# W5500_Tessel_mikroBUS_Click_005.net
KiCad netlist of a schematic drawn in EAGLE
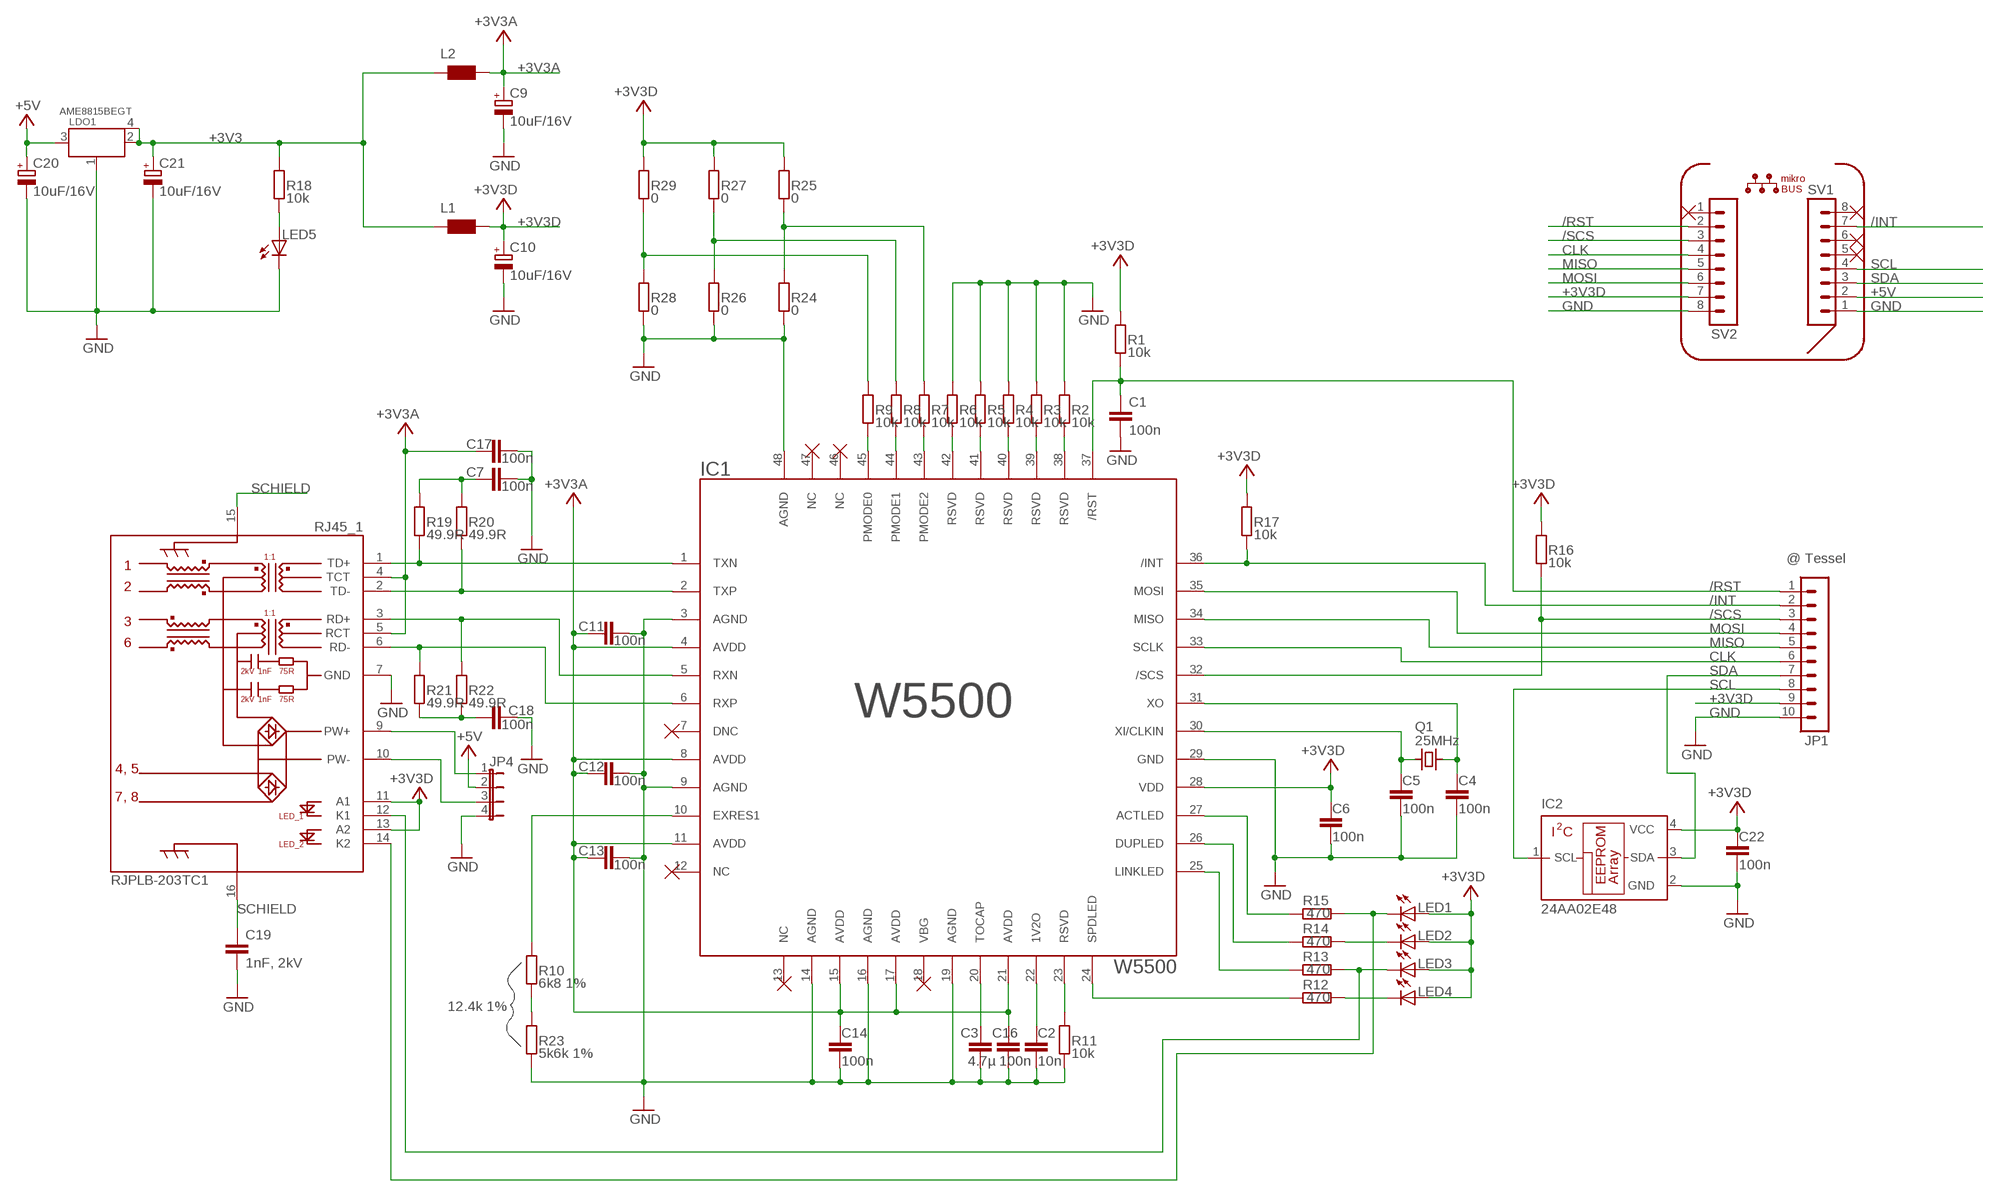
[diagram p0: schematic, sheet 1]

(export (version "E")
  (design (tool "Eeschema 10.0.6"))
  (components
    (comp (ref "C1")
      (value "100n")
      (footprint "eagle-import:C0603K")
      (libsource (lib "eagle-import") (part "C-EUC0603K"))
    )
    (comp (ref "C2")
      (value "10n")
      (footprint "eagle-import:C0402K")
      (libsource (lib "eagle-import") (part "C-EUC0402K"))
    )
    (comp (ref "C3")
      (value "4.7µ")
      (footprint "eagle-import:C0603K")
      (libsource (lib "eagle-import") (part "C-EUC0603K"))
    )
    (comp (ref "C4")
      (value "100n")
      (footprint "eagle-import:C0402K")
      (libsource (lib "eagle-import") (part "C-EUC0402K"))
    )
    (comp (ref "C5")
      (value "100n")
      (footprint "eagle-import:C0402K")
      (libsource (lib "eagle-import") (part "C-EUC0402K"))
    )
    (comp (ref "C6")
      (value "100n")
      (footprint "eagle-import:C0402K")
      (libsource (lib "eagle-import") (part "C-EUC0402K"))
    )
    (comp (ref "C7")
      (value "100n")
      (footprint "eagle-import:C0402K")
      (libsource (lib "eagle-import") (part "C-EUC0402K"))
    )
    (comp (ref "C9")
      (value "10uF/16V")
      (footprint "eagle-import:A_3216-18R")
      (libsource (lib "eagle-import") (part "CPOL-EUA/3216-18R"))
    )
    (comp (ref "C10")
      (value "10uF/16V")
      (footprint "eagle-import:A_3216-18R")
      (libsource (lib "eagle-import") (part "CPOL-EUA/3216-18R"))
    )
    (comp (ref "C11")
      (value "100n")
      (footprint "eagle-import:C0402K")
      (libsource (lib "eagle-import") (part "C-EUC0402K"))
    )
    (comp (ref "C12")
      (value "100n")
      (footprint "eagle-import:C0402K")
      (libsource (lib "eagle-import") (part "C-EUC0402K"))
    )
    (comp (ref "C13")
      (value "100n")
      (footprint "eagle-import:C0402K")
      (libsource (lib "eagle-import") (part "C-EUC0402K"))
    )
    (comp (ref "C14")
      (value "100n")
      (footprint "eagle-import:C0402K")
      (libsource (lib "eagle-import") (part "C-EUC0402K"))
    )
    (comp (ref "C16")
      (value "100n")
      (footprint "eagle-import:C0402K")
      (libsource (lib "eagle-import") (part "C-EUC0402K"))
    )
    (comp (ref "C17")
      (value "100n")
      (footprint "eagle-import:C0402K")
      (libsource (lib "eagle-import") (part "C-EUC0402K"))
    )
    (comp (ref "C18")
      (value "100n")
      (footprint "eagle-import:C0402K")
      (libsource (lib "eagle-import") (part "C-EUC0402K"))
    )
    (comp (ref "C19")
      (value "1nF, 2kV")
      (footprint "eagle-import:C3216")
      (libsource (lib "eagle-import") (part "C-EUC3216"))
    )
    (comp (ref "C20")
      (value "10uF/16V")
      (footprint "eagle-import:A_3216-18R")
      (libsource (lib "eagle-import") (part "CPOL-EUA/3216-18R"))
    )
    (comp (ref "C21")
      (value "10uF/16V")
      (footprint "eagle-import:A_3216-18R")
      (libsource (lib "eagle-import") (part "CPOL-EUA/3216-18R"))
    )
    (comp (ref "C22")
      (value "100n")
      (footprint "eagle-import:C0402K")
      (libsource (lib "eagle-import") (part "C-EUC0402K"))
    )
    (comp (ref "IC1")
      (value "W5500")
      (footprint "eagle-import:LQFP48")
      (libsource (lib "eagle-import") (part "W5500"))
    )
    (comp (ref "IC2")
      (value "24AA02E48")
      (footprint "eagle-import:SOT23-5L")
      (fields (field (name "MF") "MICROCHIP") (field (name "MPN") "24AA00T-I/OTG"))
      (libsource (lib "eagle-import") (part "2400OTAA"))
    )
    (comp (ref "JP1")
      (value "@ Tessel")
      (footprint "eagle-import:MA10-1")
      (libsource (lib "eagle-import") (part "MA10-1"))
    )
    (comp (ref "JP4")
      (value "JP4E")
      (footprint "eagle-import:JP4")
      (libsource (lib "eagle-import") (part "JP4E"))
    )
    (comp (ref "L1")
      (value "WE-CBF_0603")
      (footprint "eagle-import:0603")
      (libsource (lib "eagle-import") (part "WE-CBF_0603"))
    )
    (comp (ref "L2")
      (value "WE-CBF_0603")
      (footprint "eagle-import:0603")
      (libsource (lib "eagle-import") (part "WE-CBF_0603"))
    )
    (comp (ref "LDO1")
      (value "AME8815BEGT")
      (footprint "eagle-import:SOT223")
      (libsource (lib "eagle-import") (part "AME8815BEGT"))
    )
    (comp (ref "LED1")
      (value "LEDCHIPLED_0603")
      (footprint "eagle-import:CHIPLED_0603")
      (libsource (lib "eagle-import") (part "LEDCHIPLED_0603"))
    )
    (comp (ref "LED2")
      (value "LEDCHIPLED_0603")
      (footprint "eagle-import:CHIPLED_0603")
      (libsource (lib "eagle-import") (part "LEDCHIPLED_0603"))
    )
    (comp (ref "LED3")
      (value "LEDCHIPLED_0603")
      (footprint "eagle-import:CHIPLED_0603")
      (libsource (lib "eagle-import") (part "LEDCHIPLED_0603"))
    )
    (comp (ref "LED4")
      (value "LEDCHIPLED_0603")
      (footprint "eagle-import:CHIPLED_0603")
      (libsource (lib "eagle-import") (part "LEDCHIPLED_0603"))
    )
    (comp (ref "LED5")
      (value "LEDCHIPLED_0603")
      (footprint "eagle-import:CHIPLED_0603")
      (libsource (lib "eagle-import") (part "LEDCHIPLED_0603"))
    )
    (comp (ref "Q1")
      (value "25MHz")
      (footprint "eagle-import:SMD02502-4")
      (libsource (lib "eagle-import") (part "SMD02502-4"))
    )
    (comp (ref "R1")
      (value "10k")
      (footprint "eagle-import:R0402")
      (libsource (lib "eagle-import") (part "R-EU_R0402"))
    )
    (comp (ref "R2")
      (value "10k")
      (footprint "eagle-import:R0402")
      (libsource (lib "eagle-import") (part "R-EU_R0402"))
    )
    (comp (ref "R3")
      (value "10k")
      (footprint "eagle-import:R0402")
      (libsource (lib "eagle-import") (part "R-EU_R0402"))
    )
    (comp (ref "R4")
      (value "10k")
      (footprint "eagle-import:R0402")
      (libsource (lib "eagle-import") (part "R-EU_R0402"))
    )
    (comp (ref "R5")
      (value "10k")
      (footprint "eagle-import:R0402")
      (libsource (lib "eagle-import") (part "R-EU_R0402"))
    )
    (comp (ref "R6")
      (value "10k")
      (footprint "eagle-import:R0402")
      (libsource (lib "eagle-import") (part "R-EU_R0402"))
    )
    (comp (ref "R7")
      (value "10k")
      (footprint "eagle-import:R0402")
      (libsource (lib "eagle-import") (part "R-EU_R0402"))
    )
    (comp (ref "R8")
      (value "10k")
      (footprint "eagle-import:R0402")
      (libsource (lib "eagle-import") (part "R-EU_R0402"))
    )
    (comp (ref "R9")
      (value "10k")
      (footprint "eagle-import:R0402")
      (libsource (lib "eagle-import") (part "R-EU_R0402"))
    )
    (comp (ref "R10")
      (value "6k8 1%")
      (footprint "eagle-import:R0402")
      (libsource (lib "eagle-import") (part "R-EU_R0402"))
    )
    (comp (ref "R11")
      (value "10k")
      (footprint "eagle-import:R0402")
      (libsource (lib "eagle-import") (part "R-EU_R0402"))
    )
    (comp (ref "R12")
      (value "470")
      (footprint "eagle-import:R0402")
      (libsource (lib "eagle-import") (part "R-EU_R0402"))
    )
    (comp (ref "R13")
      (value "470")
      (footprint "eagle-import:R0402")
      (libsource (lib "eagle-import") (part "R-EU_R0402"))
    )
    (comp (ref "R14")
      (value "470")
      (footprint "eagle-import:R0402")
      (libsource (lib "eagle-import") (part "R-EU_R0402"))
    )
    (comp (ref "R15")
      (value "470")
      (footprint "eagle-import:R0402")
      (libsource (lib "eagle-import") (part "R-EU_R0402"))
    )
    (comp (ref "R16")
      (value "10k")
      (footprint "eagle-import:R0402")
      (libsource (lib "eagle-import") (part "R-EU_R0402"))
    )
    (comp (ref "R17")
      (value "10k")
      (footprint "eagle-import:R0402")
      (libsource (lib "eagle-import") (part "R-EU_R0402"))
    )
    (comp (ref "R18")
      (value "10k")
      (footprint "eagle-import:R0402")
      (libsource (lib "eagle-import") (part "R-EU_R0402"))
    )
    (comp (ref "R19")
      (value "49.9R")
      (footprint "eagle-import:R0402")
      (libsource (lib "eagle-import") (part "R-EU_R0402"))
    )
    (comp (ref "R20")
      (value "49.9R")
      (footprint "eagle-import:R0402")
      (libsource (lib "eagle-import") (part "R-EU_R0402"))
    )
    (comp (ref "R21")
      (value "49.9R")
      (footprint "eagle-import:R0402")
      (libsource (lib "eagle-import") (part "R-EU_R0402"))
    )
    (comp (ref "R22")
      (value "49.9R")
      (footprint "eagle-import:R0402")
      (libsource (lib "eagle-import") (part "R-EU_R0402"))
    )
    (comp (ref "R23")
      (value "5k6k 1%")
      (footprint "eagle-import:R0402")
      (libsource (lib "eagle-import") (part "R-EU_R0402"))
    )
    (comp (ref "R24")
      (value "0")
      (footprint "eagle-import:R0402")
      (libsource (lib "eagle-import") (part "R-EU_R0402"))
    )
    (comp (ref "R25")
      (value "0")
      (footprint "eagle-import:R0402")
      (libsource (lib "eagle-import") (part "R-EU_R0402"))
    )
    (comp (ref "R26")
      (value "0")
      (footprint "eagle-import:R0402")
      (libsource (lib "eagle-import") (part "R-EU_R0402"))
    )
    (comp (ref "R27")
      (value "0")
      (footprint "eagle-import:R0402")
      (libsource (lib "eagle-import") (part "R-EU_R0402"))
    )
    (comp (ref "R28")
      (value "0")
      (footprint "eagle-import:R0402")
      (libsource (lib "eagle-import") (part "R-EU_R0402"))
    )
    (comp (ref "R29")
      (value "0")
      (footprint "eagle-import:R0402")
      (libsource (lib "eagle-import") (part "R-EU_R0402"))
    )
    (comp (ref "RJ45_1")
      (value "RJPLB-203TC1")
      (footprint "eagle-import:RJPLB-203")
      (libsource (lib "eagle-import") (part "RJPLB-203TC1"))
    )
    (comp (ref "SV1")
      (value "MA08-1")
      (footprint "eagle-import:MA08-1")
      (libsource (lib "eagle-import") (part "MA08-1"))
    )
    (comp (ref "SV2")
      (value "MA08-1")
      (footprint "eagle-import:MA08-1")
      (libsource (lib "eagle-import") (part "MA08-1"))
    )
  )
  (nets
    (net (code "1") (name "+3V3A") (class "Default")
      (node (ref "C11") (pin "1") (pinfunction "1_1") (pintype "passive"))
      (node (ref "C12") (pin "1") (pinfunction "1_1") (pintype "passive"))
      (node (ref "C13") (pin "1") (pinfunction "1_1") (pintype "passive"))
      (node (ref "C14") (pin "1") (pinfunction "1_1") (pintype "passive"))
      (node (ref "C16") (pin "1") (pinfunction "1_1") (pintype "passive"))
      (node (ref "C17") (pin "1") (pinfunction "1_1") (pintype "passive"))
      (node (ref "C9") (pin "+") (pinfunction "+_+") (pintype "passive"))
      (node (ref "IC1") (pin "11") (pinfunction "AVDD_11") (pintype "bidirectional"))
      (node (ref "IC1") (pin "15") (pinfunction "AVDD_15") (pintype "bidirectional"))
      (node (ref "IC1") (pin "17") (pinfunction "AVDD_17") (pintype "bidirectional"))
      (node (ref "IC1") (pin "21") (pinfunction "AVDD_21") (pintype "bidirectional"))
      (node (ref "IC1") (pin "4") (pinfunction "AVDD_4") (pintype "bidirectional"))
      (node (ref "IC1") (pin "8") (pinfunction "AVDD_8") (pintype "bidirectional"))
      (node (ref "L2") (pin "1") (pinfunction "1_1") (pintype "passive"))
      (node (ref "RJ45_1") (pin "4") (pinfunction "TCT_4") (pintype "bidirectional"))
      (node (ref "RJ45_1") (pin "5") (pinfunction "RCT_5") (pintype "bidirectional"))
    )
    (net (code "2") (name "+3V3D") (class "Default")
      (node (ref "C10") (pin "+") (pinfunction "+_+") (pintype "passive"))
      (node (ref "C22") (pin "1") (pinfunction "1_1") (pintype "passive"))
      (node (ref "C6") (pin "1") (pinfunction "1_1") (pintype "passive"))
      (node (ref "IC1") (pin "28") (pinfunction "VDD_28") (pintype "bidirectional"))
      (node (ref "IC2") (pin "4") (pinfunction "VCC_4") (pintype "power_in"))
      (node (ref "JP1") (pin "9") (pinfunction "9_9") (pintype "passive"))
      (node (ref "L1") (pin "1") (pinfunction "1_1") (pintype "passive"))
      (node (ref "LED1") (pin "A") (pinfunction "A_A") (pintype "passive"))
      (node (ref "LED2") (pin "A") (pinfunction "A_A") (pintype "passive"))
      (node (ref "LED3") (pin "A") (pinfunction "A_A") (pintype "passive"))
      (node (ref "LED4") (pin "A") (pinfunction "A_A") (pintype "passive"))
      (node (ref "R1") (pin "2") (pinfunction "2_2") (pintype "passive"))
      (node (ref "R16") (pin "2") (pinfunction "2_2") (pintype "passive"))
      (node (ref "R17") (pin "2") (pinfunction "2_2") (pintype "passive"))
      (node (ref "R25") (pin "2") (pinfunction "2_2") (pintype "passive"))
      (node (ref "R27") (pin "2") (pinfunction "2_2") (pintype "passive"))
      (node (ref "R29") (pin "2") (pinfunction "2_2") (pintype "passive"))
      (node (ref "RJ45_1") (pin "11") (pinfunction "A1_11") (pintype "bidirectional"))
      (node (ref "RJ45_1") (pin "13") (pinfunction "A2_13") (pintype "bidirectional"))
      (node (ref "SV2") (pin "7") (pinfunction "7_7") (pintype "passive"))
    )
    (net (code "3") (name "+5V") (class "Default")
      (node (ref "C20") (pin "+") (pinfunction "+_+") (pintype "passive"))
      (node (ref "JP4") (pin "2") (pinfunction "2_2") (pintype "passive"))
      (node (ref "LDO1") (pin "3") (pinfunction "P$3_3") (pintype "bidirectional"))
      (node (ref "SV1") (pin "2") (pinfunction "2_2") (pintype "passive"))
    )
    (net (code "4") (name "/+3V3") (class "Default")
      (node (ref "C21") (pin "+") (pinfunction "+_+") (pintype "passive"))
      (node (ref "L1") (pin "2") (pinfunction "2_2") (pintype "passive"))
      (node (ref "L2") (pin "2") (pinfunction "2_2") (pintype "passive"))
      (node (ref "LDO1") (pin "2") (pinfunction "P$2_2") (pintype "bidirectional"))
      (node (ref "LDO1") (pin "4") (pinfunction "P$4_4") (pintype "bidirectional"))
      (node (ref "R18") (pin "2") (pinfunction "2_2") (pintype "passive"))
    )
    (net (code "5") (name "/CLK") (class "Default")
      (node (ref "IC1") (pin "33") (pinfunction "SCLK_33") (pintype "bidirectional"))
      (node (ref "JP1") (pin "6") (pinfunction "6_6") (pintype "passive"))
      (node (ref "SV2") (pin "4") (pinfunction "4_4") (pintype "passive"))
    )
    (net (code "6") (name "/MISO") (class "Default")
      (node (ref "IC1") (pin "34") (pinfunction "MISO_34") (pintype "bidirectional"))
      (node (ref "JP1") (pin "5") (pinfunction "5_5") (pintype "passive"))
      (node (ref "SV2") (pin "5") (pinfunction "5_5") (pintype "passive"))
    )
    (net (code "7") (name "/MOSI") (class "Default")
      (node (ref "IC1") (pin "35") (pinfunction "MOSI_35") (pintype "bidirectional"))
      (node (ref "JP1") (pin "4") (pinfunction "4_4") (pintype "passive"))
      (node (ref "SV2") (pin "6") (pinfunction "6_6") (pintype "passive"))
    )
    (net (code "8") (name "/SCHIELD") (class "Default")
      (node (ref "C19") (pin "1") (pinfunction "1_1") (pintype "passive"))
      (node (ref "RJ45_1") (pin "15") (pinfunction "SCHIELD_1_15") (pintype "bidirectional"))
      (node (ref "RJ45_1") (pin "16") (pinfunction "SCHIELD_2_16") (pintype "bidirectional"))
    )
    (net (code "9") (name "/SCL") (class "Default")
      (node (ref "IC2") (pin "1") (pinfunction "SCL_1") (pintype "input"))
      (node (ref "JP1") (pin "8") (pinfunction "8_8") (pintype "passive"))
      (node (ref "SV1") (pin "4") (pinfunction "4_4") (pintype "passive"))
    )
    (net (code "10") (name "/SDA") (class "Default")
      (node (ref "IC2") (pin "3") (pinfunction "SDA_3") (pintype "bidirectional"))
      (node (ref "JP1") (pin "7") (pinfunction "7_7") (pintype "passive"))
      (node (ref "SV1") (pin "3") (pinfunction "3_3") (pintype "passive"))
    )
    (net (code "11") (name "/{slash}INT") (class "Default")
      (node (ref "IC1") (pin "36") (pinfunction "/INT_36") (pintype "bidirectional"))
      (node (ref "JP1") (pin "2") (pinfunction "2_2") (pintype "passive"))
      (node (ref "R17") (pin "1") (pinfunction "1_1") (pintype "passive"))
      (node (ref "SV1") (pin "7") (pinfunction "7_7") (pintype "passive"))
    )
    (net (code "12") (name "/{slash}RST") (class "Default")
      (node (ref "C1") (pin "1") (pinfunction "1_1") (pintype "passive"))
      (node (ref "IC1") (pin "37") (pinfunction "/RST_37") (pintype "bidirectional"))
      (node (ref "JP1") (pin "1") (pinfunction "1_1") (pintype "passive"))
      (node (ref "R1") (pin "1") (pinfunction "1_1") (pintype "passive"))
      (node (ref "SV2") (pin "2") (pinfunction "2_2") (pintype "passive"))
    )
    (net (code "13") (name "/{slash}SCS") (class "Default")
      (node (ref "IC1") (pin "32") (pinfunction "/SCS_32") (pintype "bidirectional"))
      (node (ref "JP1") (pin "3") (pinfunction "3_3") (pintype "passive"))
      (node (ref "R16") (pin "1") (pinfunction "1_1") (pintype "passive"))
      (node (ref "SV2") (pin "3") (pinfunction "3_3") (pintype "passive"))
    )
    (net (code "14") (name "GND") (class "Default")
      (node (ref "C1") (pin "2") (pinfunction "2_2") (pintype "passive"))
      (node (ref "C10") (pin "-") (pinfunction "-_-") (pintype "passive"))
      (node (ref "C11") (pin "2") (pinfunction "2_2") (pintype "passive"))
      (node (ref "C12") (pin "2") (pinfunction "2_2") (pintype "passive"))
      (node (ref "C13") (pin "2") (pinfunction "2_2") (pintype "passive"))
      (node (ref "C14") (pin "2") (pinfunction "2_2") (pintype "passive"))
      (node (ref "C16") (pin "2") (pinfunction "2_2") (pintype "passive"))
      (node (ref "C17") (pin "2") (pinfunction "2_2") (pintype "passive"))
      (node (ref "C18") (pin "2") (pinfunction "2_2") (pintype "passive"))
      (node (ref "C19") (pin "2") (pinfunction "2_2") (pintype "passive"))
      (node (ref "C2") (pin "2") (pinfunction "2_2") (pintype "passive"))
      (node (ref "C20") (pin "-") (pinfunction "-_-") (pintype "passive"))
      (node (ref "C21") (pin "-") (pinfunction "-_-") (pintype "passive"))
      (node (ref "C22") (pin "2") (pinfunction "2_2") (pintype "passive"))
      (node (ref "C3") (pin "2") (pinfunction "2_2") (pintype "passive"))
      (node (ref "C4") (pin "2") (pinfunction "2_2") (pintype "passive"))
      (node (ref "C5") (pin "2") (pinfunction "2_2") (pintype "passive"))
      (node (ref "C6") (pin "2") (pinfunction "2_2") (pintype "passive"))
      (node (ref "C7") (pin "2") (pinfunction "2_2") (pintype "passive"))
      (node (ref "C9") (pin "-") (pinfunction "-_-") (pintype "passive"))
      (node (ref "IC1") (pin "14") (pinfunction "AGND_14") (pintype "bidirectional"))
      (node (ref "IC1") (pin "16") (pinfunction "AGND_16") (pintype "bidirectional"))
      (node (ref "IC1") (pin "19") (pinfunction "AGND_19") (pintype "bidirectional"))
      (node (ref "IC1") (pin "29") (pinfunction "GND_29") (pintype "bidirectional"))
      (node (ref "IC1") (pin "3") (pinfunction "AGND_3") (pintype "bidirectional"))
      (node (ref "IC1") (pin "48") (pinfunction "AGND_48") (pintype "bidirectional"))
      (node (ref "IC1") (pin "9") (pinfunction "AGND_9") (pintype "bidirectional"))
      (node (ref "IC2") (pin "2") (pinfunction "GND_2") (pintype "power_in"))
      (node (ref "JP1") (pin "10") (pinfunction "10_10") (pintype "passive"))
      (node (ref "JP4") (pin "4") (pinfunction "4_4") (pintype "passive"))
      (node (ref "LDO1") (pin "1") (pinfunction "P$1_1") (pintype "bidirectional"))
      (node (ref "LED5") (pin "C") (pinfunction "C_C") (pintype "passive"))
      (node (ref "R11") (pin "1") (pinfunction "1_1") (pintype "passive"))
      (node (ref "R2") (pin "2") (pinfunction "2_2") (pintype "passive"))
      (node (ref "R23") (pin "1") (pinfunction "1_1") (pintype "passive"))
      (node (ref "R24") (pin "1") (pinfunction "1_1") (pintype "passive"))
      (node (ref "R26") (pin "1") (pinfunction "1_1") (pintype "passive"))
      (node (ref "R28") (pin "1") (pinfunction "1_1") (pintype "passive"))
      (node (ref "R3") (pin "2") (pinfunction "2_2") (pintype "passive"))
      (node (ref "R4") (pin "2") (pinfunction "2_2") (pintype "passive"))
      (node (ref "R5") (pin "2") (pinfunction "2_2") (pintype "passive"))
      (node (ref "R6") (pin "2") (pinfunction "2_2") (pintype "passive"))
      (node (ref "RJ45_1") (pin "7") (pinfunction "GND_7") (pintype "bidirectional"))
      (node (ref "SV1") (pin "1") (pinfunction "1_1") (pintype "passive"))
      (node (ref "SV2") (pin "8") (pinfunction "8_8") (pintype "passive"))
    )
    (net (code "15") (name "Net-(C7-Pad1)") (class "Default")
      (node (ref "C7") (pin "1") (pinfunction "1_1") (pintype "passive"))
      (node (ref "R19") (pin "2") (pinfunction "2_2") (pintype "passive"))
      (node (ref "R20") (pin "2") (pinfunction "2_2") (pintype "passive"))
    )
    (net (code "16") (name "Net-(C18-Pad1)") (class "Default")
      (node (ref "C18") (pin "1") (pinfunction "1_1") (pintype "passive"))
      (node (ref "R21") (pin "1") (pinfunction "1_1") (pintype "passive"))
      (node (ref "R22") (pin "1") (pinfunction "1_1") (pintype "passive"))
    )
    (net (code "17") (name "Net-(IC1-1V2O)") (class "Default")
      (node (ref "C2") (pin "1") (pinfunction "1_1") (pintype "passive"))
      (node (ref "IC1") (pin "22") (pinfunction "1V2O_22") (pintype "bidirectional"))
    )
    (net (code "18") (name "Net-(IC1-ACTLED)") (class "Default")
      (node (ref "IC1") (pin "27") (pinfunction "ACTLED_27") (pintype "bidirectional"))
      (node (ref "R15") (pin "1") (pinfunction "1_1") (pintype "passive"))
    )
    (net (code "19") (name "Net-(IC1-DUPLED)") (class "Default")
      (node (ref "IC1") (pin "26") (pinfunction "DUPLED_26") (pintype "bidirectional"))
      (node (ref "R14") (pin "1") (pinfunction "1_1") (pintype "passive"))
    )
    (net (code "20") (name "Net-(IC1-EXRES1)") (class "Default")
      (node (ref "IC1") (pin "10") (pinfunction "EXRES1_10") (pintype "bidirectional"))
      (node (ref "R10") (pin "2") (pinfunction "2_2") (pintype "passive"))
    )
    (net (code "21") (name "Net-(IC1-LINKLED)") (class "Default")
      (node (ref "IC1") (pin "25") (pinfunction "LINKLED_25") (pintype "bidirectional"))
      (node (ref "R13") (pin "1") (pinfunction "1_1") (pintype "passive"))
    )
    (net (code "22") (name "Net-(IC1-PMODE0)") (class "Default")
      (node (ref "IC1") (pin "45") (pinfunction "PMODE0_45") (pintype "bidirectional"))
      (node (ref "R9") (pin "1") (pinfunction "1_1") (pintype "passive"))
    )
    (net (code "23") (name "Net-(IC1-PMODE1)") (class "Default")
      (node (ref "IC1") (pin "44") (pinfunction "PMODE1_44") (pintype "bidirectional"))
      (node (ref "R8") (pin "1") (pinfunction "1_1") (pintype "passive"))
    )
    (net (code "24") (name "Net-(IC1-PMODE2)") (class "Default")
      (node (ref "IC1") (pin "43") (pinfunction "PMODE2_43") (pintype "bidirectional"))
      (node (ref "R7") (pin "1") (pinfunction "1_1") (pintype "passive"))
    )
    (net (code "25") (name "Net-(IC1-RSVD-Pad23)") (class "Default")
      (node (ref "IC1") (pin "23") (pinfunction "RSVD_23") (pintype "bidirectional"))
      (node (ref "R11") (pin "2") (pinfunction "2_2") (pintype "passive"))
    )
    (net (code "26") (name "Net-(IC1-RSVD-Pad38)") (class "Default")
      (node (ref "IC1") (pin "38") (pinfunction "RSVD_38") (pintype "bidirectional"))
      (node (ref "R2") (pin "1") (pinfunction "1_1") (pintype "passive"))
    )
    (net (code "27") (name "Net-(IC1-RSVD-Pad39)") (class "Default")
      (node (ref "IC1") (pin "39") (pinfunction "RSVD_39") (pintype "bidirectional"))
      (node (ref "R3") (pin "1") (pinfunction "1_1") (pintype "passive"))
    )
    (net (code "28") (name "Net-(IC1-RSVD-Pad40)") (class "Default")
      (node (ref "IC1") (pin "40") (pinfunction "RSVD_40") (pintype "bidirectional"))
      (node (ref "R4") (pin "1") (pinfunction "1_1") (pintype "passive"))
    )
    (net (code "29") (name "Net-(IC1-RSVD-Pad41)") (class "Default")
      (node (ref "IC1") (pin "41") (pinfunction "RSVD_41") (pintype "bidirectional"))
      (node (ref "R5") (pin "1") (pinfunction "1_1") (pintype "passive"))
    )
    (net (code "30") (name "Net-(IC1-RSVD-Pad42)") (class "Default")
      (node (ref "IC1") (pin "42") (pinfunction "RSVD_42") (pintype "bidirectional"))
      (node (ref "R6") (pin "1") (pinfunction "1_1") (pintype "passive"))
    )
    (net (code "31") (name "Net-(IC1-RXN)") (class "Default")
      (node (ref "IC1") (pin "5") (pinfunction "RXN_5") (pintype "bidirectional"))
      (node (ref "R22") (pin "2") (pinfunction "2_2") (pintype "passive"))
      (node (ref "RJ45_1") (pin "3") (pinfunction "RD+_3") (pintype "bidirectional"))
    )
    (net (code "32") (name "Net-(IC1-RXP)") (class "Default")
      (node (ref "IC1") (pin "6") (pinfunction "RXP_6") (pintype "bidirectional"))
      (node (ref "R21") (pin "2") (pinfunction "2_2") (pintype "passive"))
      (node (ref "RJ45_1") (pin "6") (pinfunction "RD-_6") (pintype "bidirectional"))
    )
    (net (code "33") (name "Net-(IC1-SPDLED)") (class "Default")
      (node (ref "IC1") (pin "24") (pinfunction "SPDLED_24") (pintype "bidirectional"))
      (node (ref "R12") (pin "1") (pinfunction "1_1") (pintype "passive"))
    )
    (net (code "34") (name "Net-(IC1-TOCAP)") (class "Default")
      (node (ref "C3") (pin "1") (pinfunction "1_1") (pintype "passive"))
      (node (ref "IC1") (pin "20") (pinfunction "TOCAP_20") (pintype "bidirectional"))
    )
    (net (code "35") (name "Net-(IC1-TXN)") (class "Default")
      (node (ref "IC1") (pin "1") (pinfunction "TXN_1") (pintype "bidirectional"))
      (node (ref "R19") (pin "1") (pinfunction "1_1") (pintype "passive"))
      (node (ref "RJ45_1") (pin "1") (pinfunction "TD+_1") (pintype "bidirectional"))
    )
    (net (code "36") (name "Net-(IC1-TXP)") (class "Default")
      (node (ref "IC1") (pin "2") (pinfunction "TXP_2") (pintype "bidirectional"))
      (node (ref "R20") (pin "1") (pinfunction "1_1") (pintype "passive"))
      (node (ref "RJ45_1") (pin "2") (pinfunction "TD-_2") (pintype "bidirectional"))
    )
    (net (code "37") (name "Net-(IC1-XI{slash}CLKIN)") (class "Default")
      (node (ref "C5") (pin "1") (pinfunction "1_1") (pintype "passive"))
      (node (ref "IC1") (pin "30") (pinfunction "XI/CLKIN_30") (pintype "bidirectional"))
      (node (ref "Q1") (pin "1") (pinfunction "1_1") (pintype "bidirectional"))
    )
    (net (code "38") (name "Net-(IC1-XO)") (class "Default")
      (node (ref "C4") (pin "1") (pinfunction "1_1") (pintype "passive"))
      (node (ref "IC1") (pin "31") (pinfunction "XO_31") (pintype "bidirectional"))
      (node (ref "Q1") (pin "3") (pinfunction "2_3") (pintype "bidirectional"))
    )
    (net (code "39") (name "Net-(LED2-PadC)") (class "Default")
      (node (ref "LED2") (pin "C") (pinfunction "C_C") (pintype "passive"))
      (node (ref "R14") (pin "2") (pinfunction "2_2") (pintype "passive"))
    )
    (net (code "40") (name "Net-(LED4-PadC)") (class "Default")
      (node (ref "LED4") (pin "C") (pinfunction "C_C") (pintype "passive"))
      (node (ref "R12") (pin "2") (pinfunction "2_2") (pintype "passive"))
    )
    (net (code "41") (name "Net-(LED5-PadA)") (class "Default")
      (node (ref "LED5") (pin "A") (pinfunction "A_A") (pintype "passive"))
      (node (ref "R18") (pin "1") (pinfunction "1_1") (pintype "passive"))
    )
    (net (code "42") (name "Net-(R10-Pad1)") (class "Default")
      (node (ref "R10") (pin "1") (pinfunction "1_1") (pintype "passive"))
      (node (ref "R23") (pin "2") (pinfunction "2_2") (pintype "passive"))
    )
    (net (code "43") (name "Net-(R24-Pad2)") (class "Default")
      (node (ref "R24") (pin "2") (pinfunction "2_2") (pintype "passive"))
      (node (ref "R25") (pin "1") (pinfunction "1_1") (pintype "passive"))
      (node (ref "R7") (pin "2") (pinfunction "2_2") (pintype "passive"))
    )
    (net (code "44") (name "Net-(R26-Pad2)") (class "Default")
      (node (ref "R26") (pin "2") (pinfunction "2_2") (pintype "passive"))
      (node (ref "R27") (pin "1") (pinfunction "1_1") (pintype "passive"))
      (node (ref "R8") (pin "2") (pinfunction "2_2") (pintype "passive"))
    )
    (net (code "45") (name "Net-(R28-Pad2)") (class "Default")
      (node (ref "R28") (pin "2") (pinfunction "2_2") (pintype "passive"))
      (node (ref "R29") (pin "1") (pinfunction "1_1") (pintype "passive"))
      (node (ref "R9") (pin "2") (pinfunction "2_2") (pintype "passive"))
    )
    (net (code "46") (name "Net-(RJ45_1-K1)") (class "Default")
      (node (ref "LED3") (pin "C") (pinfunction "C_C") (pintype "passive"))
      (node (ref "R13") (pin "2") (pinfunction "2_2") (pintype "passive"))
      (node (ref "RJ45_1") (pin "12") (pinfunction "K1_12") (pintype "bidirectional"))
    )
    (net (code "47") (name "Net-(RJ45_1-K2)") (class "Default")
      (node (ref "LED1") (pin "C") (pinfunction "C_C") (pintype "passive"))
      (node (ref "R15") (pin "2") (pinfunction "2_2") (pintype "passive"))
      (node (ref "RJ45_1") (pin "14") (pinfunction "K2_14") (pintype "bidirectional"))
    )
    (net (code "48") (name "Net-(RJ45_1-PW+)") (class "Default")
      (node (ref "JP4") (pin "1") (pinfunction "1_1") (pintype "passive"))
      (node (ref "RJ45_1") (pin "9") (pinfunction "PW+_9") (pintype "bidirectional"))
    )
    (net (code "49") (name "Net-(RJ45_1-PW-)") (class "Default")
      (node (ref "JP4") (pin "3") (pinfunction "3_3") (pintype "passive"))
      (node (ref "RJ45_1") (pin "10") (pinfunction "PW-_10") (pintype "bidirectional"))
    )
    (net (code "50") (name "unconnected-(IC1-DNC-Pad7)") (class "Default")
      (node (ref "IC1") (pin "7") (pinfunction "DNC_7") (pintype "bidirectional"))
    )
    (net (code "51") (name "unconnected-(IC1-NC-Pad12)") (class "Default")
      (node (ref "IC1") (pin "12") (pinfunction "NC_12") (pintype "bidirectional"))
    )
    (net (code "52") (name "unconnected-(IC1-NC-Pad13)") (class "Default")
      (node (ref "IC1") (pin "13") (pinfunction "NC_13") (pintype "bidirectional"))
    )
    (net (code "53") (name "unconnected-(IC1-NC-Pad46)") (class "Default")
      (node (ref "IC1") (pin "46") (pinfunction "NC_46") (pintype "bidirectional"))
    )
    (net (code "54") (name "unconnected-(IC1-NC-Pad47)") (class "Default")
      (node (ref "IC1") (pin "47") (pinfunction "NC_47") (pintype "bidirectional"))
    )
    (net (code "55") (name "unconnected-(IC1-VBG-Pad18)") (class "Default")
      (node (ref "IC1") (pin "18") (pinfunction "VBG_18") (pintype "bidirectional"))
    )
    (net (code "56") (name "unconnected-(SV1-Pad5)") (class "Default")
      (node (ref "SV1") (pin "5") (pinfunction "5_5") (pintype "passive"))
    )
    (net (code "57") (name "unconnected-(SV1-Pad6)") (class "Default")
      (node (ref "SV1") (pin "6") (pinfunction "6_6") (pintype "passive"))
    )
    (net (code "58") (name "unconnected-(SV1-Pad8)") (class "Default")
      (node (ref "SV1") (pin "8") (pinfunction "8_8") (pintype "passive"))
    )
    (net (code "59") (name "unconnected-(SV2-Pad1)") (class "Default")
      (node (ref "SV2") (pin "1") (pinfunction "1_1") (pintype "passive"))
    )
  )
)
